# Sheet3.net
KiCad netlist of a schematic drawn in Altium Designer
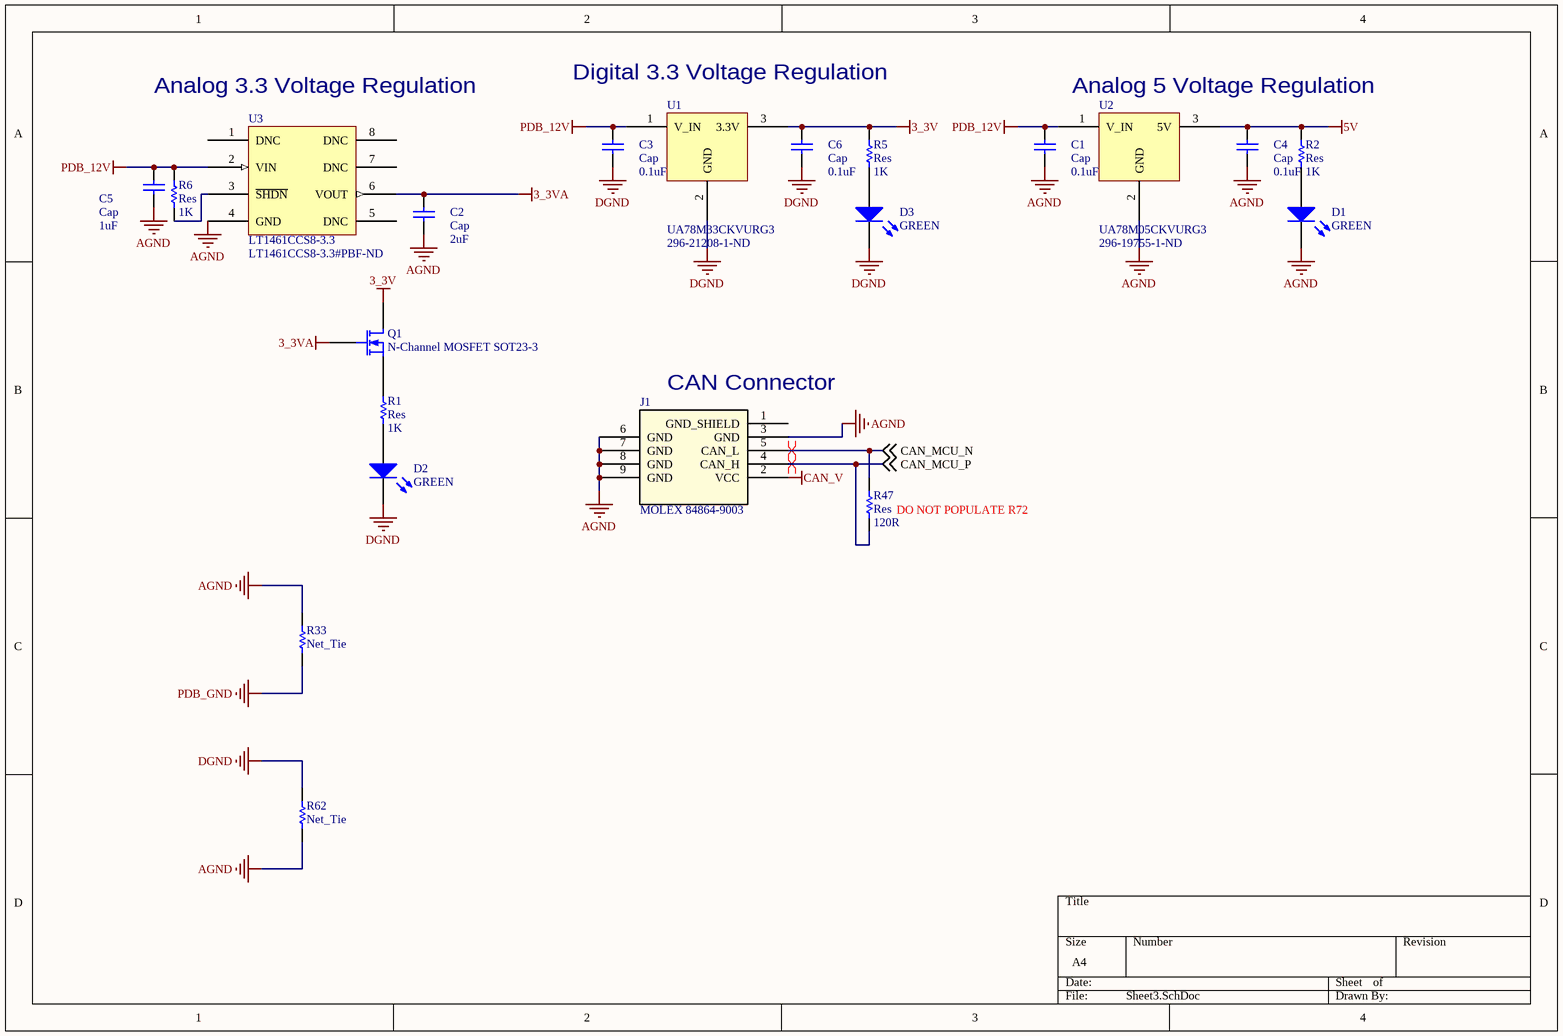
[diagram p0: Sheet3.SchDoc]

(export (version "E")
  (design (tool "Eeschema 10.0.6"))
  (components
    (comp (ref "C1")
      (value "Cap")
      (footprint "C1206")
      (description "Capacitor")
      (fields (field (name "ALTIUM_VALUE") "0.1uF") (field (name "PUBLISHER") "Altium Limited"))
      (libsource (lib "Capacitors") (part "Cap"))
    )
    (comp (ref "C2")
      (value "Cap")
      (footprint "C1206")
      (description "Capacitor")
      (fields (field (name "ALTIUM_VALUE") "2uF") (field (name "PUBLISHER") "Altium Limited"))
      (libsource (lib "Capacitors") (part "Cap"))
    )
    (comp (ref "C3")
      (value "Cap")
      (footprint "C1206")
      (description "Capacitor")
      (fields (field (name "ALTIUM_VALUE") "0.1uF") (field (name "PUBLISHER") "Altium Limited"))
      (libsource (lib "Capacitors") (part "Cap"))
    )
    (comp (ref "C4")
      (value "Cap")
      (footprint "C1206")
      (description "Capacitor")
      (fields (field (name "ALTIUM_VALUE") "0.1uF") (field (name "PUBLISHER") "Altium Limited"))
      (libsource (lib "Capacitors") (part "Cap"))
    )
    (comp (ref "C5")
      (value "Cap")
      (footprint "C1206")
      (description "Capacitor")
      (fields (field (name "ALTIUM_VALUE") "1uF") (field (name "PUBLISHER") "Altium Limited"))
      (libsource (lib "Capacitors") (part "Cap"))
    )
    (comp (ref "C6")
      (value "Cap")
      (footprint "C1206")
      (description "Capacitor")
      (fields (field (name "ALTIUM_VALUE") "0.1uF") (field (name "PUBLISHER") "Altium Limited"))
      (libsource (lib "Capacitors") (part "Cap"))
    )
    (comp (ref "D1")
      (value "OVS5MGBCR4")
      (footprint "OVS5MGBCR4")
      (description "Typical GREEN LED")
      (fields (field (name "COLOUR") "GREEN") (field (name "PUBLISHER") "Altium Limited"))
      (libsource (lib "LEDs") (part "OVS5MGBCR4"))
    )
    (comp (ref "D2")
      (value "OVS5MGBCR4")
      (footprint "OVS5MGBCR4")
      (description "Typical GREEN LED")
      (fields (field (name "COLOUR") "GREEN") (field (name "PUBLISHER") "Altium Limited"))
      (libsource (lib "LEDs") (part "OVS5MGBCR4"))
    )
    (comp (ref "D3")
      (value "OVS5MGBCR4")
      (footprint "OVS5MGBCR4")
      (description "Typical GREEN LED")
      (fields (field (name "COLOUR") "GREEN") (field (name "PUBLISHER") "Altium Limited"))
      (libsource (lib "LEDs") (part "OVS5MGBCR4"))
    )
    (comp (ref "J1")
      (value "MOLEX 84864-9003")
      (footprint "MOLEX 84864-9003")
      (description "CAN Micro-Change M12, Right Angle, Male")
      (libsource (lib "Connectors and Headers") (part "MOLEX 84864-9003"))
    )
    (comp (ref "Q1")
      (value "N-Channel MOSFET SOT23-3")
      (footprint "SOT23-3")
      (libsource (lib "Transistors") (part "MOSFET-N SOT23-3"))
    )
    (comp (ref "R1")
      (value "Res")
      (footprint "2012[0805]")
      (description "Surface Mount Resistor")
      (fields (field (name "ALTIUM_VALUE") "1K") (field (name "PUBLISHER") "Altium Limited"))
      (libsource (lib "Resistors") (part "Res"))
    )
    (comp (ref "R2")
      (value "Res")
      (footprint "2012[0805]")
      (description "Surface Mount Resistor")
      (fields (field (name "ALTIUM_VALUE") "1K") (field (name "PUBLISHER") "Altium Limited"))
      (libsource (lib "Resistors") (part "Res"))
    )
    (comp (ref "R5")
      (value "Res")
      (footprint "2012[0805]")
      (description "Surface Mount Resistor")
      (fields (field (name "ALTIUM_VALUE") "1K") (field (name "PUBLISHER") "Altium Limited"))
      (libsource (lib "Resistors") (part "Res"))
    )
    (comp (ref "R6")
      (value "Res")
      (footprint "2012[0805]")
      (description "Surface Mount Resistor")
      (fields (field (name "ALTIUM_VALUE") "1K") (field (name "PUBLISHER") "Altium Limited"))
      (libsource (lib "Resistors") (part "Res"))
    )
    (comp (ref "R33")
      (value "Net_Tie")
      (footprint "NetTie 0805 40mil")
      (description "Surface Mount Resistor")
      (libsource (lib "Resistors") (part "Res_NetTie"))
    )
    (comp (ref "R47")
      (value "Res")
      (footprint "2012[0805]")
      (description "Surface Mount Resistor")
      (fields (field (name "ALTIUM_VALUE") "120R") (field (name "PUBLISHER") "Altium Limited"))
      (libsource (lib "Resistors") (part "Res"))
    )
    (comp (ref "R62")
      (value "Net_Tie")
      (footprint "NetTie 0805 40mil")
      (description "Surface Mount Resistor")
      (libsource (lib "Resistors") (part "Res_NetTie"))
    )
    (comp (ref "U1")
      (value "UA78M33CKVURG3")
      (footprint "TO-252-3")
      (description "3.3V Regulator")
      (fields (field (name "SUPPLIER PART NUMBER 1") "296-21208-1-ND"))
      (libsource (lib "Voltage Regulation") (part "UA78M33CKVURG3"))
    )
    (comp (ref "U2")
      (value "UA78M05CKVURG3")
      (footprint "TO-252-3")
      (description "5.0V Regulator")
      (fields (field (name "SUPPLIER PART NUMBER 1") "296-19755-1-ND"))
      (libsource (lib "Voltage Regulation") (part "UA78M05CKVURG3"))
    )
    (comp (ref "U3")
      (value "LT1461CCS8-3.3")
      (footprint "SOIC-8-150")
      (description "IC VREF SERIES 3.3V 8SOIC")
      (fields (field (name "SUPPLIER PART NUMBER 1") "LT1461CCS8-3.3#PBF-ND"))
      (libsource (lib "Voltage Regulation") (part "LT1461CCS8-3.3"))
    )
  )
  (nets
    (net (code "1") (name "3_3V") (class "Default")
      (node (ref "C6") (pin "2") (pinfunction "2_2") (pintype "passive"))
      (node (ref "Q1") (pin "3") (pinfunction "D_3") (pintype "passive"))
      (node (ref "R5") (pin "2") (pinfunction "2_2") (pintype "passive"))
      (node (ref "U1") (pin "3") (pinfunction "3.3V_3") (pintype "passive"))
    )
    (net (code "2") (name "3_3VA") (class "Default")
      (node (ref "C2") (pin "2") (pinfunction "2_2") (pintype "passive"))
      (node (ref "Q1") (pin "1") (pinfunction "G_1") (pintype "passive"))
      (node (ref "U3") (pin "6") (pinfunction "VOUT_6") (pintype "output"))
    )
    (net (code "3") (name "5V") (class "Default")
      (node (ref "C4") (pin "2") (pinfunction "2_2") (pintype "passive"))
      (node (ref "R2") (pin "2") (pinfunction "2_2") (pintype "passive"))
      (node (ref "U2") (pin "3") (pinfunction "5V_3") (pintype "passive"))
    )
    (net (code "4") (name "AGND") (class "Default")
      (node (ref "C1") (pin "1") (pinfunction "1_1") (pintype "passive"))
      (node (ref "C2") (pin "1") (pinfunction "1_1") (pintype "passive"))
      (node (ref "C4") (pin "1") (pinfunction "1_1") (pintype "passive"))
      (node (ref "C5") (pin "1") (pinfunction "1_1") (pintype "passive"))
      (node (ref "D1") (pin "2") (pinfunction "K_2") (pintype "passive"))
      (node (ref "J1") (pin "3") (pinfunction "GND_3") (pintype "passive"))
      (node (ref "J1") (pin "6") (pinfunction "GND_6") (pintype "passive"))
      (node (ref "J1") (pin "7") (pinfunction "GND_7") (pintype "passive"))
      (node (ref "J1") (pin "8") (pinfunction "GND_8") (pintype "passive"))
      (node (ref "J1") (pin "9") (pinfunction "GND_9") (pintype "passive"))
      (node (ref "R33") (pin "2") (pinfunction "2_2") (pintype "passive"))
      (node (ref "R62") (pin "1") (pinfunction "1_1") (pintype "passive"))
      (node (ref "U2") (pin "2") (pinfunction "GND_2") (pintype "passive"))
      (node (ref "U3") (pin "4") (pinfunction "GND_4") (pintype "power_in"))
    )
    (net (code "5") (name "CAN_MCU_N") (class "Default")
      (node (ref "J1") (pin "5") (pinfunction "CAN_L_5") (pintype "passive"))
      (node (ref "R47") (pin "1") (pinfunction "1_1") (pintype "passive"))
    )
    (net (code "6") (name "CAN_MCU_P") (class "Default")
      (node (ref "J1") (pin "4") (pinfunction "CAN_H_4") (pintype "passive"))
      (node (ref "R47") (pin "2") (pinfunction "2_2") (pintype "passive"))
    )
    (net (code "7") (name "CAN_V") (class "Default")
      (node (ref "J1") (pin "2") (pinfunction "VCC_2") (pintype "passive"))
    )
    (net (code "8") (name "DGND") (class "Default")
      (node (ref "C3") (pin "1") (pinfunction "1_1") (pintype "passive"))
      (node (ref "C6") (pin "1") (pinfunction "1_1") (pintype "passive"))
      (node (ref "D2") (pin "2") (pinfunction "K_2") (pintype "passive"))
      (node (ref "D3") (pin "2") (pinfunction "K_2") (pintype "passive"))
      (node (ref "R62") (pin "2") (pinfunction "2_2") (pintype "passive"))
      (node (ref "U1") (pin "2") (pinfunction "GND_2") (pintype "passive"))
    )
    (net (code "9") (name "Net-(D1-A)") (class "Default")
      (node (ref "D1") (pin "1") (pinfunction "A_1") (pintype "passive"))
      (node (ref "R2") (pin "1") (pinfunction "1_1") (pintype "passive"))
    )
    (net (code "10") (name "Net-(D2-A)") (class "Default")
      (node (ref "D2") (pin "1") (pinfunction "A_1") (pintype "passive"))
      (node (ref "R1") (pin "1") (pinfunction "1_1") (pintype "passive"))
    )
    (net (code "11") (name "Net-(D3-A)") (class "Default")
      (node (ref "D3") (pin "1") (pinfunction "A_1") (pintype "passive"))
      (node (ref "R5") (pin "1") (pinfunction "1_1") (pintype "passive"))
    )
    (net (code "12") (name "Net-(Q1-S)") (class "Default")
      (node (ref "Q1") (pin "2") (pinfunction "S_2") (pintype "passive"))
      (node (ref "R1") (pin "2") (pinfunction "2_2") (pintype "passive"))
    )
    (net (code "13") (name "Net-(U3-~{SHDN})") (class "Default")
      (node (ref "R6") (pin "1") (pinfunction "1_1") (pintype "passive"))
      (node (ref "U3") (pin "3") (pinfunction "~{SHDN}_3") (pintype "passive"))
    )
    (net (code "14") (name "PDB_12V") (class "Default")
      (node (ref "C1") (pin "2") (pinfunction "2_2") (pintype "passive"))
      (node (ref "C3") (pin "2") (pinfunction "2_2") (pintype "passive"))
      (node (ref "C5") (pin "2") (pinfunction "2_2") (pintype "passive"))
      (node (ref "R6") (pin "2") (pinfunction "2_2") (pintype "passive"))
      (node (ref "U1") (pin "1") (pinfunction "V_IN_1") (pintype "passive"))
      (node (ref "U2") (pin "1") (pinfunction "V_IN_1") (pintype "passive"))
      (node (ref "U3") (pin "2") (pinfunction "VIN_2") (pintype "input"))
    )
    (net (code "15") (name "PDB_GND") (class "Default")
      (node (ref "R33") (pin "1") (pinfunction "1_1") (pintype "passive"))
    )
    (net (code "16") (name "unconnected-(J1-GND_SHIELD-Pad1)") (class "Default")
      (node (ref "J1") (pin "1") (pinfunction "GND_SHIELD_1") (pintype "passive"))
    )
    (net (code "17") (name "unconnected-(U3-DNC-Pad1)") (class "Default")
      (node (ref "U3") (pin "1") (pinfunction "DNC_1") (pintype "passive"))
    )
    (net (code "18") (name "unconnected-(U3-DNC-Pad5)") (class "Default")
      (node (ref "U3") (pin "5") (pinfunction "DNC_5") (pintype "passive"))
    )
    (net (code "19") (name "unconnected-(U3-DNC-Pad7)") (class "Default")
      (node (ref "U3") (pin "7") (pinfunction "DNC_7") (pintype "passive"))
    )
    (net (code "20") (name "unconnected-(U3-DNC-Pad8)") (class "Default")
      (node (ref "U3") (pin "8") (pinfunction "DNC_8") (pintype "passive"))
    )
  )
)
